# Campesinoi2c.net
KiCad netlist of a schematic drawn in EAGLE
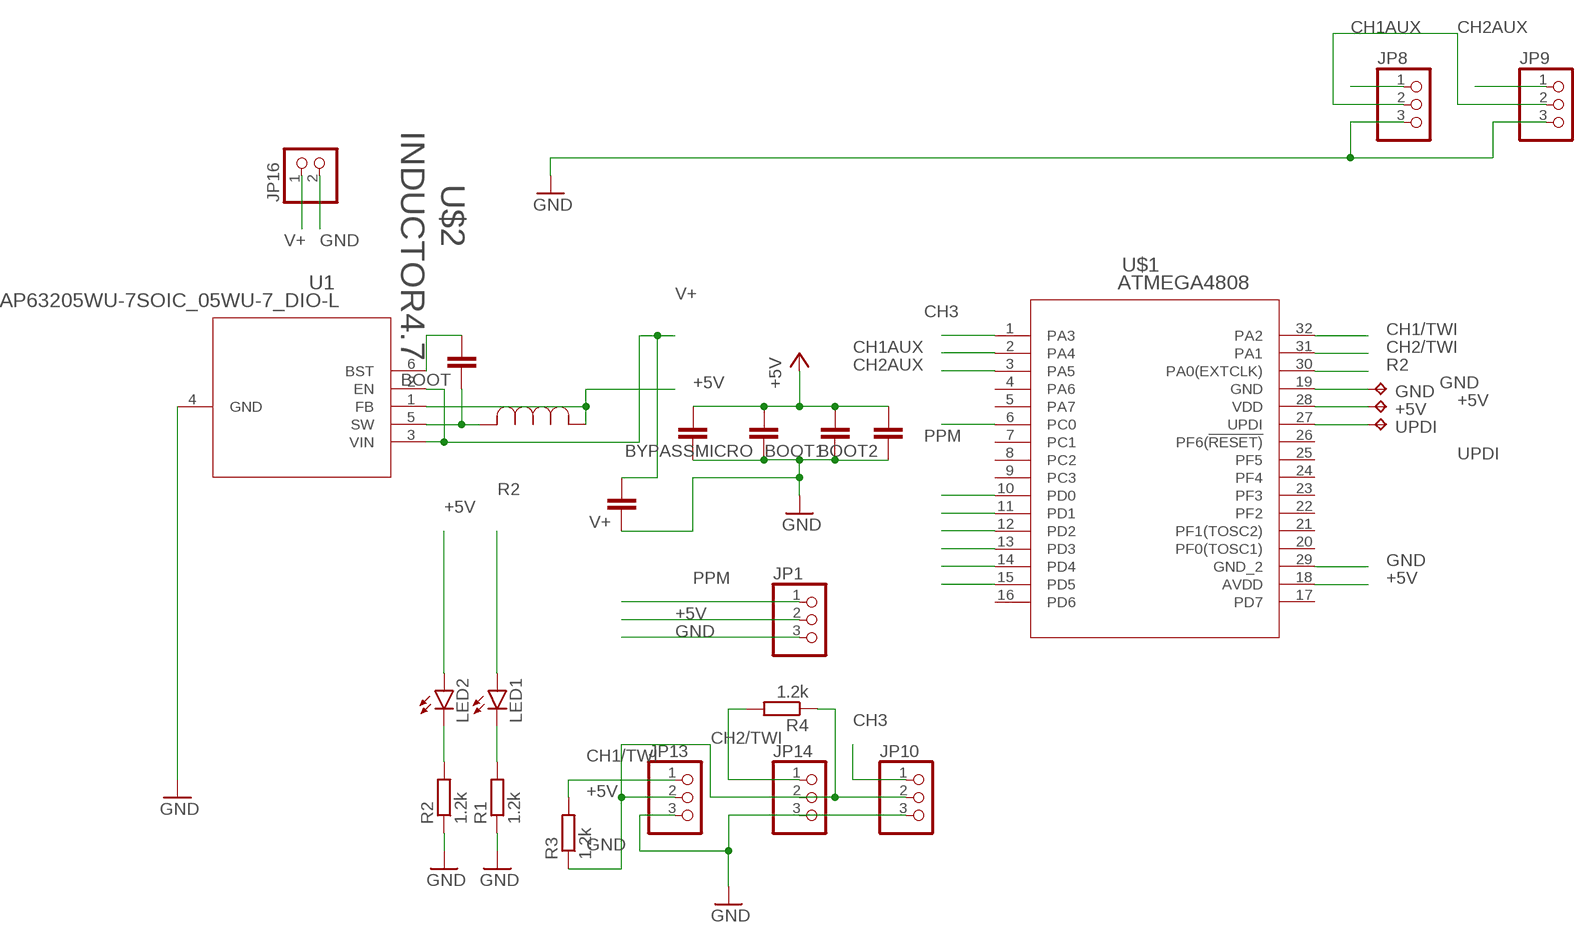
[diagram p0: schematic, sheet 1]

(export (version "E")
  (design (tool "Eeschema 10.0.6"))
  (components
    (comp (ref "+5V")
      (value "TPB1,27")
      (footprint "eagle-import:B1,27")
      (libsource (lib "eagle-import") (part "TPB1,27"))
    )
    (comp (ref "BOOT")
      (value "C-EUC0402")
      (footprint "eagle-import:C0402")
      (libsource (lib "eagle-import") (part "C-EUC0402"))
    )
    (comp (ref "BOOT1")
      (value "C-EUC0402")
      (footprint "eagle-import:C0402")
      (libsource (lib "eagle-import") (part "C-EUC0402"))
    )
    (comp (ref "BOOT2")
      (value "C-EUC0402")
      (footprint "eagle-import:C0402")
      (libsource (lib "eagle-import") (part "C-EUC0402"))
    )
    (comp (ref "BYPASSMICRO")
      (value "C-EUC0603")
      (footprint "eagle-import:C0603")
      (libsource (lib "eagle-import") (part "C-EUC0603"))
    )
    (comp (ref "BYPASSMICRO2")
      (value "C-EUC0603")
      (footprint "eagle-import:C0603")
      (libsource (lib "eagle-import") (part "C-EUC0603"))
    )
    (comp (ref "GND")
      (value "TPB1,27")
      (footprint "eagle-import:B1,27")
      (libsource (lib "eagle-import") (part "TPB1,27"))
    )
    (comp (ref "JP1")
      (value "PINHD-1X03_2.54-S")
      (footprint "eagle-import:1X03-S")
      (libsource (lib "eagle-import") (part "PINHD-1X03_2.54-S"))
    )
    (comp (ref "JP8")
      (value "PINHD-1X03_2.54-S")
      (footprint "eagle-import:1X03-S")
      (libsource (lib "eagle-import") (part "PINHD-1X03_2.54-S"))
    )
    (comp (ref "JP9")
      (value "PINHD-1X03_2.54-S")
      (footprint "eagle-import:1X03-S")
      (libsource (lib "eagle-import") (part "PINHD-1X03_2.54-S"))
    )
    (comp (ref "JP10")
      (value "PINHD-1X03_2.54-S")
      (footprint "eagle-import:1X03-S")
      (libsource (lib "eagle-import") (part "PINHD-1X03_2.54-S"))
    )
    (comp (ref "JP13")
      (value "PINHD-1X03_2.54-S")
      (footprint "eagle-import:1X03-S")
      (libsource (lib "eagle-import") (part "PINHD-1X03_2.54-S"))
    )
    (comp (ref "JP14")
      (value "PINHD-1X03_2.54-S")
      (footprint "eagle-import:1X03-S")
      (libsource (lib "eagle-import") (part "PINHD-1X03_2.54-S"))
    )
    (comp (ref "JP16")
      (value "PINHD-1X02_2.54-S")
      (footprint "eagle-import:1X02-S")
      (libsource (lib "eagle-import") (part "PINHD-1X02_2.54-S"))
    )
    (comp (ref "LED1")
      (value "LEDCHIPLED_0603")
      (footprint "eagle-import:CHIPLED_0603")
      (libsource (lib "eagle-import") (part "LEDCHIPLED_0603"))
    )
    (comp (ref "LED2")
      (value "LEDCHIPLED_0603")
      (footprint "eagle-import:CHIPLED_0603")
      (libsource (lib "eagle-import") (part "LEDCHIPLED_0603"))
    )
    (comp (ref "R1")
      (value "1.2k")
      (footprint "eagle-import:R0603")
      (libsource (lib "eagle-import") (part "R-EU_R0603"))
    )
    (comp (ref "R2")
      (value "1.2k")
      (footprint "eagle-import:R0603")
      (libsource (lib "eagle-import") (part "R-EU_R0603"))
    )
    (comp (ref "R3")
      (value "1.2k")
      (footprint "eagle-import:R0603")
      (libsource (lib "eagle-import") (part "R-EU_R0603"))
    )
    (comp (ref "R4")
      (value "1.2k")
      (footprint "eagle-import:R0603")
      (libsource (lib "eagle-import") (part "R-EU_R0603"))
    )
    (comp (ref "U$1")
      (value "ATMEGA4808")
      (footprint "eagle-import:QFP80P900X900X120-32N")
      (libsource (lib "eagle-import") (part "ATMEGA4808"))
    )
    (comp (ref "U$2")
      (value "INDUCTOR4.7")
      (footprint "eagle-import:IND_NRS5030T100MMGJ_TAY")
      (libsource (lib "eagle-import") (part "INDUCTOR4.7"))
    )
    (comp (ref "U1")
      (value "AP63205WU-7SOIC_05WU-7_DIO-L")
      (footprint "eagle-import:SOIC_05WU-7_DIO-L")
      (fields
        (field (name "MANUFACTURER_PART_NUMBER") "AP63205WU-7")
        (field (name "COPYRIGHT") "Copyright (C) 2018 Accelerated Designs. All rights reserved")
      )
      (libsource (lib "eagle-import") (part "AP63205WU-7SOIC_05WU-7_DIO-L"))
    )
    (comp (ref "UPDI")
      (value "TPB1,27")
      (footprint "eagle-import:B1,27")
      (libsource (lib "eagle-import") (part "TPB1,27"))
    )
    (comp (ref "V+")
      (value "C-EUC1206")
      (footprint "eagle-import:C1206")
      (libsource (lib "eagle-import") (part "C-EUC1206"))
    )
  )
  (nets
    (net (code "1") (name "+5V") (class "Default")
      (node (ref "+5V") (pin "TP") (pinfunction "TP_TP") (pintype "input"))
      (node (ref "BOOT1") (pin "2") (pinfunction "2_2") (pintype "passive"))
      (node (ref "BOOT2") (pin "2") (pinfunction "2_2") (pintype "passive"))
      (node (ref "BYPASSMICRO") (pin "2") (pinfunction "2_2") (pintype "passive"))
      (node (ref "BYPASSMICRO2") (pin "2") (pinfunction "2_2") (pintype "passive"))
      (node (ref "JP1") (pin "2") (pinfunction "2_2") (pintype "passive"))
      (node (ref "JP10") (pin "2") (pinfunction "2_2") (pintype "passive"))
      (node (ref "JP13") (pin "2") (pinfunction "2_2") (pintype "passive"))
      (node (ref "JP14") (pin "2") (pinfunction "2_2") (pintype "passive"))
      (node (ref "JP8") (pin "2") (pinfunction "2_2") (pintype "passive"))
      (node (ref "JP9") (pin "2") (pinfunction "2_2") (pintype "passive"))
      (node (ref "LED2") (pin "A") (pinfunction "A_A") (pintype "passive"))
      (node (ref "R3") (pin "1") (pinfunction "1_1") (pintype "passive"))
      (node (ref "R4") (pin "1") (pinfunction "1_1") (pintype "passive"))
      (node (ref "U$1") (pin "18") (pinfunction "AVDD_18") (pintype "power_in"))
      (node (ref "U$1") (pin "28") (pinfunction "VDD_28") (pintype "power_in"))
      (node (ref "U$2") (pin "1") (pinfunction "1_1") (pintype "passive"))
      (node (ref "U1") (pin "1") (pinfunction "FB_1") (pintype "passive"))
    )
    (net (code "2") (name "/CH1AUX") (class "Default")
      (node (ref "JP8") (pin "1") (pinfunction "1_1") (pintype "passive"))
      (node (ref "U$1") (pin "2") (pinfunction "PA4_2") (pintype "bidirectional"))
    )
    (net (code "3") (name "/CH1{slash}TWI") (class "Default")
      (node (ref "JP13") (pin "1") (pinfunction "1_1") (pintype "passive"))
      (node (ref "R3") (pin "2") (pinfunction "2_2") (pintype "passive"))
      (node (ref "U$1") (pin "32") (pinfunction "PA2_32") (pintype "bidirectional"))
    )
    (net (code "4") (name "/CH2AUX") (class "Default")
      (node (ref "JP9") (pin "1") (pinfunction "1_1") (pintype "passive"))
      (node (ref "U$1") (pin "3") (pinfunction "PA5_3") (pintype "bidirectional"))
    )
    (net (code "5") (name "/CH2{slash}TWI") (class "Default")
      (node (ref "JP14") (pin "1") (pinfunction "1_1") (pintype "passive"))
      (node (ref "R4") (pin "2") (pinfunction "2_2") (pintype "passive"))
      (node (ref "U$1") (pin "31") (pinfunction "PA1_31") (pintype "bidirectional"))
    )
    (net (code "6") (name "/CH3") (class "Default")
      (node (ref "JP10") (pin "1") (pinfunction "1_1") (pintype "passive"))
      (node (ref "U$1") (pin "1") (pinfunction "PA3_1") (pintype "bidirectional"))
    )
    (net (code "7") (name "/PPM") (class "Default")
      (node (ref "JP1") (pin "1") (pinfunction "1_1") (pintype "passive"))
      (node (ref "U$1") (pin "6") (pinfunction "PC0_6") (pintype "bidirectional"))
    )
    (net (code "8") (name "/R2") (class "Default")
      (node (ref "LED1") (pin "A") (pinfunction "A_A") (pintype "passive"))
      (node (ref "U$1") (pin "30") (pinfunction "PA0(EXTCLK)_30") (pintype "bidirectional"))
    )
    (net (code "9") (name "/UPDI") (class "Default")
      (node (ref "U$1") (pin "27") (pinfunction "UPDI_27") (pintype "bidirectional"))
      (node (ref "UPDI") (pin "TP") (pinfunction "TP_TP") (pintype "input"))
    )
    (net (code "10") (name "/V+") (class "Default")
      (node (ref "JP16") (pin "1") (pinfunction "1_1") (pintype "passive"))
      (node (ref "U1") (pin "2") (pinfunction "EN_2") (pintype "passive"))
      (node (ref "U1") (pin "3") (pinfunction "VIN_3") (pintype "passive"))
      (node (ref "V+") (pin "2") (pinfunction "2_2") (pintype "passive"))
    )
    (net (code "11") (name "GND") (class "Default")
      (node (ref "BOOT1") (pin "1") (pinfunction "1_1") (pintype "passive"))
      (node (ref "BOOT2") (pin "1") (pinfunction "1_1") (pintype "passive"))
      (node (ref "BYPASSMICRO") (pin "1") (pinfunction "1_1") (pintype "passive"))
      (node (ref "BYPASSMICRO2") (pin "1") (pinfunction "1_1") (pintype "passive"))
      (node (ref "GND") (pin "TP") (pinfunction "TP_TP") (pintype "input"))
      (node (ref "JP1") (pin "3") (pinfunction "3_3") (pintype "passive"))
      (node (ref "JP10") (pin "3") (pinfunction "3_3") (pintype "passive"))
      (node (ref "JP13") (pin "3") (pinfunction "3_3") (pintype "passive"))
      (node (ref "JP14") (pin "3") (pinfunction "3_3") (pintype "passive"))
      (node (ref "JP16") (pin "2") (pinfunction "2_2") (pintype "passive"))
      (node (ref "JP8") (pin "3") (pinfunction "3_3") (pintype "passive"))
      (node (ref "JP9") (pin "3") (pinfunction "3_3") (pintype "passive"))
      (node (ref "R1") (pin "1") (pinfunction "1_1") (pintype "passive"))
      (node (ref "R2") (pin "1") (pinfunction "1_1") (pintype "passive"))
      (node (ref "U$1") (pin "19") (pinfunction "GND_19") (pintype "passive"))
      (node (ref "U$1") (pin "29") (pinfunction "GND_2_29") (pintype "passive"))
      (node (ref "U1") (pin "4") (pinfunction "GND_4") (pintype "passive"))
      (node (ref "V+") (pin "1") (pinfunction "1_1") (pintype "passive"))
    )
    (net (code "12") (name "Net-(LED1-PadC)") (class "Default")
      (node (ref "LED1") (pin "C") (pinfunction "C_C") (pintype "passive"))
      (node (ref "R1") (pin "2") (pinfunction "2_2") (pintype "passive"))
    )
    (net (code "13") (name "Net-(LED2-PadC)") (class "Default")
      (node (ref "LED2") (pin "C") (pinfunction "C_C") (pintype "passive"))
      (node (ref "R2") (pin "2") (pinfunction "2_2") (pintype "passive"))
    )
    (net (code "14") (name "Net-(U1-BST)") (class "Default")
      (node (ref "BOOT") (pin "2") (pinfunction "2_2") (pintype "passive"))
      (node (ref "U1") (pin "6") (pinfunction "BST_6") (pintype "passive"))
    )
    (net (code "15") (name "Net-(U1-SW)") (class "Default")
      (node (ref "BOOT") (pin "1") (pinfunction "1_1") (pintype "passive"))
      (node (ref "U$2") (pin "2") (pinfunction "2_2") (pintype "passive"))
      (node (ref "U1") (pin "5") (pinfunction "SW_5") (pintype "passive"))
    )
    (net (code "16") (name "unconnected-(U$1-PA6-Pad4)") (class "Default")
      (node (ref "U$1") (pin "4") (pinfunction "PA6_4") (pintype "bidirectional"))
    )
    (net (code "17") (name "unconnected-(U$1-PA7-Pad5)") (class "Default")
      (node (ref "U$1") (pin "5") (pinfunction "PA7_5") (pintype "bidirectional"))
    )
    (net (code "18") (name "unconnected-(U$1-PC1-Pad7)") (class "Default")
      (node (ref "U$1") (pin "7") (pinfunction "PC1_7") (pintype "bidirectional"))
    )
    (net (code "19") (name "unconnected-(U$1-PC2-Pad8)") (class "Default")
      (node (ref "U$1") (pin "8") (pinfunction "PC2_8") (pintype "bidirectional"))
    )
    (net (code "20") (name "unconnected-(U$1-PC3-Pad9)") (class "Default")
      (node (ref "U$1") (pin "9") (pinfunction "PC3_9") (pintype "bidirectional"))
    )
    (net (code "21") (name "unconnected-(U$1-PD0-Pad10)") (class "Default")
      (node (ref "U$1") (pin "10") (pinfunction "PD0_10") (pintype "bidirectional"))
    )
    (net (code "22") (name "unconnected-(U$1-PD1-Pad11)") (class "Default")
      (node (ref "U$1") (pin "11") (pinfunction "PD1_11") (pintype "bidirectional"))
    )
    (net (code "23") (name "unconnected-(U$1-PD2-Pad12)") (class "Default")
      (node (ref "U$1") (pin "12") (pinfunction "PD2_12") (pintype "bidirectional"))
    )
    (net (code "24") (name "unconnected-(U$1-PD3-Pad13)") (class "Default")
      (node (ref "U$1") (pin "13") (pinfunction "PD3_13") (pintype "bidirectional"))
    )
    (net (code "25") (name "unconnected-(U$1-PD4-Pad14)") (class "Default")
      (node (ref "U$1") (pin "14") (pinfunction "PD4_14") (pintype "bidirectional"))
    )
    (net (code "26") (name "unconnected-(U$1-PD5-Pad15)") (class "Default")
      (node (ref "U$1") (pin "15") (pinfunction "PD5_15") (pintype "bidirectional"))
    )
    (net (code "27") (name "unconnected-(U$1-PD6-Pad16)") (class "Default")
      (node (ref "U$1") (pin "16") (pinfunction "PD6_16") (pintype "bidirectional"))
    )
    (net (code "28") (name "unconnected-(U$1-PD7-Pad17)") (class "Default")
      (node (ref "U$1") (pin "17") (pinfunction "PD7_17") (pintype "bidirectional"))
    )
    (net (code "29") (name "unconnected-(U$1-PF0(TOSC1)-Pad20)") (class "Default")
      (node (ref "U$1") (pin "20") (pinfunction "PF0(TOSC1)_20") (pintype "bidirectional"))
    )
    (net (code "30") (name "unconnected-(U$1-PF1(TOSC2)-Pad21)") (class "Default")
      (node (ref "U$1") (pin "21") (pinfunction "PF1(TOSC2)_21") (pintype "bidirectional"))
    )
    (net (code "31") (name "unconnected-(U$1-PF2-Pad22)") (class "Default")
      (node (ref "U$1") (pin "22") (pinfunction "PF2_22") (pintype "bidirectional"))
    )
    (net (code "32") (name "unconnected-(U$1-PF3-Pad23)") (class "Default")
      (node (ref "U$1") (pin "23") (pinfunction "PF3_23") (pintype "bidirectional"))
    )
    (net (code "33") (name "unconnected-(U$1-PF4-Pad24)") (class "Default")
      (node (ref "U$1") (pin "24") (pinfunction "PF4_24") (pintype "bidirectional"))
    )
    (net (code "34") (name "unconnected-(U$1-PF5-Pad25)") (class "Default")
      (node (ref "U$1") (pin "25") (pinfunction "PF5_25") (pintype "bidirectional"))
    )
    (net (code "35") (name "unconnected-(U$1-PF6(~{RESET})-Pad26)") (class "Default")
      (node (ref "U$1") (pin "26") (pinfunction "PF6(~{RESET})_26") (pintype "bidirectional"))
    )
  )
)
